# analog_filterung.net
KiCad netlist of a schematic drawn in Altium Designer
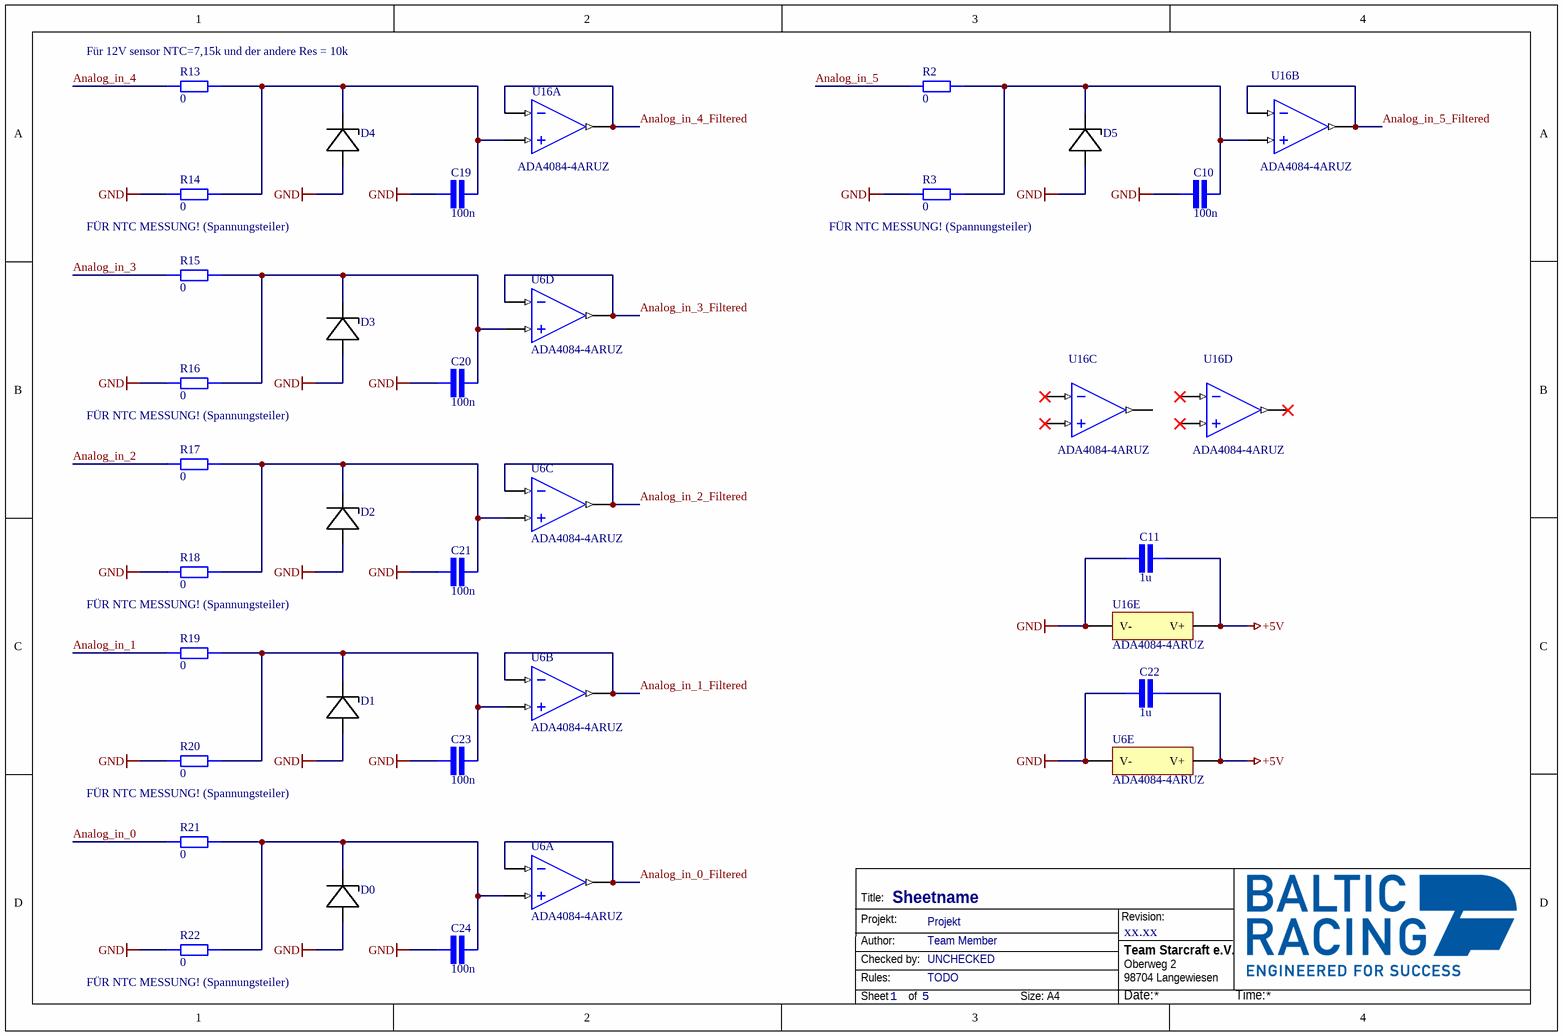
[diagram p0: analog filterung.SchDoc]

(export (version "E")
  (design (tool "Eeschema 10.0.6"))
  (components
    (comp (ref "C10")
      (value "100n")
      (footprint "CAP 0603/1608")
      (description "Capacitor with multiple Footprints")
      (fields (field (name "Comment") "SMD Capacitor"))
      (libsource (lib "") (part "SMD Capacitor_1"))
    )
    (comp (ref "C11")
      (value "1u")
      (footprint "CAP 0603/1608")
      (description "Capacitor with multiple Footprints")
      (fields (field (name "Comment") "SMD Capacitor"))
      (libsource (lib "Standardbauteile") (part "SMD Capacitor"))
    )
    (comp (ref "C19")
      (value "100n")
      (footprint "CAP 0603/1608")
      (description "Capacitor with multiple Footprints")
      (fields (field (name "Comment") "SMD Capacitor"))
      (libsource (lib "") (part "SMD Capacitor_1"))
    )
    (comp (ref "C20")
      (value "100n")
      (footprint "CAP 0603/1608")
      (description "Capacitor with multiple Footprints")
      (fields (field (name "Comment") "SMD Capacitor"))
      (libsource (lib "") (part "SMD Capacitor_1"))
    )
    (comp (ref "C21")
      (value "100n")
      (footprint "CAP 0603/1608")
      (description "Capacitor with multiple Footprints")
      (fields (field (name "Comment") "SMD Capacitor"))
      (libsource (lib "") (part "SMD Capacitor_1"))
    )
    (comp (ref "C22")
      (value "1u")
      (footprint "CAP 0603/1608")
      (description "Capacitor with multiple Footprints")
      (fields (field (name "Comment") "SMD Capacitor"))
      (libsource (lib "Standardbauteile") (part "SMD Capacitor"))
    )
    (comp (ref "C23")
      (value "100n")
      (footprint "CAP 0603/1608")
      (description "Capacitor with multiple Footprints")
      (fields (field (name "Comment") "SMD Capacitor"))
      (libsource (lib "") (part "SMD Capacitor_1"))
    )
    (comp (ref "C24")
      (value "100n")
      (footprint "CAP 0603/1608")
      (description "Capacitor with multiple Footprints")
      (fields (field (name "Comment") "SMD Capacitor"))
      (libsource (lib "") (part "SMD Capacitor_1"))
    )
    (comp (ref "D0")
      (value "MMBZ4625-HE3-08")
      (footprint "SOT95P248X115-3N")
      (description "Zener-Diode 5.1 Volt 0.225W 5% AUTO")
      (libsource (lib "LibMoritz") (part "MMBZ4625-HE3-08"))
    )
    (comp (ref "D1")
      (value "MMBZ4625-HE3-08")
      (footprint "SOT95P248X115-3N")
      (description "Zener-Diode 5.1 Volt 0.225W 5% AUTO")
      (libsource (lib "LibMoritz") (part "MMBZ4625-HE3-08"))
    )
    (comp (ref "D2")
      (value "MMBZ4625-HE3-08")
      (footprint "SOT95P248X115-3N")
      (description "Zener-Diode 5.1 Volt 0.225W 5% AUTO")
      (libsource (lib "LibMoritz") (part "MMBZ4625-HE3-08"))
    )
    (comp (ref "D3")
      (value "MMBZ4625-HE3-08")
      (footprint "SOT95P248X115-3N")
      (description "Zener-Diode 5.1 Volt 0.225W 5% AUTO")
      (libsource (lib "LibMoritz") (part "MMBZ4625-HE3-08"))
    )
    (comp (ref "D4")
      (value "MMBZ4625-HE3-08")
      (footprint "SOT95P248X115-3N")
      (description "Zener-Diode 5.1 Volt 0.225W 5% AUTO")
      (libsource (lib "LibMoritz") (part "MMBZ4625-HE3-08"))
    )
    (comp (ref "D5")
      (value "MMBZ4625-HE3-08")
      (footprint "SOT95P248X115-3N")
      (description "Zener-Diode 5.1 Volt 0.225W 5% AUTO")
      (libsource (lib "LibMoritz") (part "MMBZ4625-HE3-08"))
    )
    (comp (ref "R2")
      (value "0")
      (footprint "STACKPOLE CSR0603")
      (description "Resistor with multiple footprints")
      (fields (field (name "Comment") "SMD Resistor"))
      (libsource (lib "Standardbauteile") (part "SMD Resistor"))
    )
    (comp (ref "R3")
      (value "0")
      (footprint "STACKPOLE CSR0603")
      (description "Resistor with multiple footprints")
      (fields (field (name "Comment") "SMD Resistor"))
      (libsource (lib "Standardbauteile") (part "SMD Resistor"))
    )
    (comp (ref "R13")
      (value "0")
      (footprint "STACKPOLE CSR0603")
      (description "Resistor with multiple footprints")
      (fields (field (name "Comment") "SMD Resistor"))
      (libsource (lib "Standardbauteile") (part "SMD Resistor"))
    )
    (comp (ref "R14")
      (value "0")
      (footprint "STACKPOLE CSR0603")
      (description "Resistor with multiple footprints")
      (fields (field (name "Comment") "SMD Resistor"))
      (libsource (lib "Standardbauteile") (part "SMD Resistor"))
    )
    (comp (ref "R15")
      (value "0")
      (footprint "STACKPOLE CSR0603")
      (description "Resistor with multiple footprints")
      (fields (field (name "Comment") "SMD Resistor"))
      (libsource (lib "Standardbauteile") (part "SMD Resistor"))
    )
    (comp (ref "R16")
      (value "0")
      (footprint "STACKPOLE CSR0603")
      (description "Resistor with multiple footprints")
      (fields (field (name "Comment") "SMD Resistor"))
      (libsource (lib "Standardbauteile") (part "SMD Resistor"))
    )
    (comp (ref "R17")
      (value "0")
      (footprint "STACKPOLE CSR0603")
      (description "Resistor with multiple footprints")
      (fields (field (name "Comment") "SMD Resistor"))
      (libsource (lib "Standardbauteile") (part "SMD Resistor"))
    )
    (comp (ref "R18")
      (value "0")
      (footprint "STACKPOLE CSR0603")
      (description "Resistor with multiple footprints")
      (fields (field (name "Comment") "SMD Resistor"))
      (libsource (lib "Standardbauteile") (part "SMD Resistor"))
    )
    (comp (ref "R19")
      (value "0")
      (footprint "STACKPOLE CSR0603")
      (description "Resistor with multiple footprints")
      (fields (field (name "Comment") "SMD Resistor"))
      (libsource (lib "Standardbauteile") (part "SMD Resistor"))
    )
    (comp (ref "R20")
      (value "0")
      (footprint "STACKPOLE CSR0603")
      (description "Resistor with multiple footprints")
      (fields (field (name "Comment") "SMD Resistor"))
      (libsource (lib "Standardbauteile") (part "SMD Resistor"))
    )
    (comp (ref "R21")
      (value "0")
      (footprint "STACKPOLE CSR0603")
      (description "Resistor with multiple footprints")
      (fields (field (name "Comment") "SMD Resistor"))
      (libsource (lib "Standardbauteile") (part "SMD Resistor"))
    )
    (comp (ref "R22")
      (value "0")
      (footprint "STACKPOLE CSR0603")
      (description "Resistor with multiple footprints")
      (fields (field (name "Comment") "SMD Resistor"))
      (libsource (lib "Standardbauteile") (part "SMD Resistor"))
    )
    (comp (ref "U6")
      (value "ADA4084-4ARUZ")
      (footprint "ANALOG_RU14")
      (description "30 V, Low Noise, Rail-to-Rail Input/Output, Low Power Operational Amplifiers")
      (libsource (lib "Standardbauteile") (part "ADA4084-4ARUZ"))
    )
    (comp (ref "U16")
      (value "ADA4084-4ARUZ")
      (footprint "ANALOG_RU14")
      (description "30 V, Low Noise, Rail-to-Rail Input/Output, Low Power Operational Amplifiers")
      (libsource (lib "Standardbauteile") (part "ADA4084-4ARUZ"))
    )
  )
  (nets
    (net (code "1") (name "+5V") (class "Default")
      (node (ref "C11") (pin "1") (pinfunction "1_1") (pintype "passive"))
      (node (ref "C22") (pin "1") (pinfunction "1_1") (pintype "passive"))
      (node (ref "U16") (pin "4") (pinfunction "V+_4") (pintype "power_in"))
      (node (ref "U6") (pin "4") (pinfunction "V+_4") (pintype "power_in"))
    )
    (net (code "2") (name "/Analog_in_0") (class "Default")
      (node (ref "R21") (pin "2") (pinfunction "2_2") (pintype "passive"))
    )
    (net (code "3") (name "/Analog_in_0_Filtered") (class "Default")
      (node (ref "U6") (pin "1") (pinfunction "OUT_A_1") (pintype "output"))
      (node (ref "U6") (pin "2") (pinfunction "-IN_A_2") (pintype "input"))
    )
    (net (code "4") (name "/Analog_in_1") (class "Default")
      (node (ref "R19") (pin "2") (pinfunction "2_2") (pintype "passive"))
    )
    (net (code "5") (name "/Analog_in_1_Filtered") (class "Default")
      (node (ref "U6") (pin "6") (pinfunction "-IN_B_6") (pintype "input"))
      (node (ref "U6") (pin "7") (pinfunction "OUT_B_7") (pintype "output"))
    )
    (net (code "6") (name "/Analog_in_2") (class "Default")
      (node (ref "R17") (pin "2") (pinfunction "2_2") (pintype "passive"))
    )
    (net (code "7") (name "/Analog_in_2_Filtered") (class "Default")
      (node (ref "U6") (pin "8") (pinfunction "OUT_C_8") (pintype "output"))
      (node (ref "U6") (pin "9") (pinfunction "-IN_C_9") (pintype "input"))
    )
    (net (code "8") (name "/Analog_in_3") (class "Default")
      (node (ref "R15") (pin "2") (pinfunction "2_2") (pintype "passive"))
    )
    (net (code "9") (name "/Analog_in_3_Filtered") (class "Default")
      (node (ref "U6") (pin "13") (pinfunction "-IN_D_13") (pintype "input"))
      (node (ref "U6") (pin "14") (pinfunction "OUT_D_14") (pintype "output"))
    )
    (net (code "10") (name "/Analog_in_4") (class "Default")
      (node (ref "R13") (pin "2") (pinfunction "2_2") (pintype "passive"))
    )
    (net (code "11") (name "/Analog_in_4_Filtered") (class "Default")
      (node (ref "U16") (pin "1") (pinfunction "OUT_A_1") (pintype "output"))
      (node (ref "U16") (pin "2") (pinfunction "-IN_A_2") (pintype "input"))
    )
    (net (code "12") (name "/Analog_in_5") (class "Default")
      (node (ref "R2") (pin "2") (pinfunction "2_2") (pintype "passive"))
    )
    (net (code "13") (name "/Analog_in_5_Filtered") (class "Default")
      (node (ref "U16") (pin "6") (pinfunction "-IN_B_6") (pintype "input"))
      (node (ref "U16") (pin "7") (pinfunction "OUT_B_7") (pintype "output"))
    )
    (net (code "14") (name "GND") (class "Default")
      (node (ref "C10") (pin "1") (pinfunction "1_1") (pintype "passive"))
      (node (ref "C11") (pin "2") (pinfunction "2_2") (pintype "passive"))
      (node (ref "C19") (pin "1") (pinfunction "1_1") (pintype "passive"))
      (node (ref "C20") (pin "1") (pinfunction "1_1") (pintype "passive"))
      (node (ref "C21") (pin "1") (pinfunction "1_1") (pintype "passive"))
      (node (ref "C22") (pin "2") (pinfunction "2_2") (pintype "passive"))
      (node (ref "C23") (pin "1") (pinfunction "1_1") (pintype "passive"))
      (node (ref "C24") (pin "1") (pinfunction "1_1") (pintype "passive"))
      (node (ref "D0") (pin "A") (pinfunction "Anode_A") (pintype "passive"))
      (node (ref "D1") (pin "A") (pinfunction "Anode_A") (pintype "passive"))
      (node (ref "D2") (pin "A") (pinfunction "Anode_A") (pintype "passive"))
      (node (ref "D3") (pin "A") (pinfunction "Anode_A") (pintype "passive"))
      (node (ref "D4") (pin "A") (pinfunction "Anode_A") (pintype "passive"))
      (node (ref "D5") (pin "A") (pinfunction "Anode_A") (pintype "passive"))
      (node (ref "R14") (pin "2") (pinfunction "2_2") (pintype "passive"))
      (node (ref "R16") (pin "2") (pinfunction "2_2") (pintype "passive"))
      (node (ref "R18") (pin "2") (pinfunction "2_2") (pintype "passive"))
      (node (ref "R20") (pin "2") (pinfunction "2_2") (pintype "passive"))
      (node (ref "R22") (pin "2") (pinfunction "2_2") (pintype "passive"))
      (node (ref "R3") (pin "2") (pinfunction "2_2") (pintype "passive"))
      (node (ref "U16") (pin "11") (pinfunction "V-_11") (pintype "power_in"))
      (node (ref "U6") (pin "11") (pinfunction "V-_11") (pintype "power_in"))
    )
    (net (code "15") (name "Net-(D0-Kathode)") (class "Default")
      (node (ref "C24") (pin "2") (pinfunction "2_2") (pintype "passive"))
      (node (ref "D0") (pin "C") (pinfunction "Kathode_C") (pintype "passive"))
      (node (ref "R21") (pin "1") (pinfunction "1_1") (pintype "passive"))
      (node (ref "R22") (pin "1") (pinfunction "1_1") (pintype "passive"))
      (node (ref "U6") (pin "3") (pinfunction "+IN_A_3") (pintype "input"))
    )
    (net (code "16") (name "Net-(D1-Kathode)") (class "Default")
      (node (ref "C23") (pin "2") (pinfunction "2_2") (pintype "passive"))
      (node (ref "D1") (pin "C") (pinfunction "Kathode_C") (pintype "passive"))
      (node (ref "R19") (pin "1") (pinfunction "1_1") (pintype "passive"))
      (node (ref "R20") (pin "1") (pinfunction "1_1") (pintype "passive"))
      (node (ref "U6") (pin "5") (pinfunction "+IN_B_5") (pintype "input"))
    )
    (net (code "17") (name "Net-(D2-Kathode)") (class "Default")
      (node (ref "C21") (pin "2") (pinfunction "2_2") (pintype "passive"))
      (node (ref "D2") (pin "C") (pinfunction "Kathode_C") (pintype "passive"))
      (node (ref "R17") (pin "1") (pinfunction "1_1") (pintype "passive"))
      (node (ref "R18") (pin "1") (pinfunction "1_1") (pintype "passive"))
      (node (ref "U6") (pin "10") (pinfunction "+IN_C_10") (pintype "input"))
    )
    (net (code "18") (name "Net-(D3-Kathode)") (class "Default")
      (node (ref "C20") (pin "2") (pinfunction "2_2") (pintype "passive"))
      (node (ref "D3") (pin "C") (pinfunction "Kathode_C") (pintype "passive"))
      (node (ref "R15") (pin "1") (pinfunction "1_1") (pintype "passive"))
      (node (ref "R16") (pin "1") (pinfunction "1_1") (pintype "passive"))
      (node (ref "U6") (pin "12") (pinfunction "+IN_D_12") (pintype "input"))
    )
    (net (code "19") (name "Net-(D4-Kathode)") (class "Default")
      (node (ref "C19") (pin "2") (pinfunction "2_2") (pintype "passive"))
      (node (ref "D4") (pin "C") (pinfunction "Kathode_C") (pintype "passive"))
      (node (ref "R13") (pin "1") (pinfunction "1_1") (pintype "passive"))
      (node (ref "R14") (pin "1") (pinfunction "1_1") (pintype "passive"))
      (node (ref "U16") (pin "3") (pinfunction "+IN_A_3") (pintype "input"))
    )
    (net (code "20") (name "Net-(D5-Kathode)") (class "Default")
      (node (ref "C10") (pin "2") (pinfunction "2_2") (pintype "passive"))
      (node (ref "D5") (pin "C") (pinfunction "Kathode_C") (pintype "passive"))
      (node (ref "R2") (pin "1") (pinfunction "1_1") (pintype "passive"))
      (node (ref "R3") (pin "1") (pinfunction "1_1") (pintype "passive"))
      (node (ref "U16") (pin "5") (pinfunction "+IN_B_5") (pintype "input"))
    )
    (net (code "21") (name "unconnected-(U16C-+IN_C-Pad10)") (class "Default")
      (node (ref "U16") (pin "10") (pinfunction "+IN_C_10") (pintype "input+no_connect"))
    )
    (net (code "22") (name "unconnected-(U16C--IN_C-Pad9)") (class "Default")
      (node (ref "U16") (pin "9") (pinfunction "-IN_C_9") (pintype "input+no_connect"))
    )
    (net (code "23") (name "unconnected-(U16C-OUT_C-Pad8)") (class "Default")
      (node (ref "U16") (pin "8") (pinfunction "OUT_C_8") (pintype "output"))
    )
    (net (code "24") (name "unconnected-(U16D-+IN_D-Pad12)") (class "Default")
      (node (ref "U16") (pin "12") (pinfunction "+IN_D_12") (pintype "input+no_connect"))
    )
    (net (code "25") (name "unconnected-(U16D--IN_D-Pad13)") (class "Default")
      (node (ref "U16") (pin "13") (pinfunction "-IN_D_13") (pintype "input+no_connect"))
    )
    (net (code "26") (name "unconnected-(U16D-OUT_D-Pad14)") (class "Default")
      (node (ref "U16") (pin "14") (pinfunction "OUT_D_14") (pintype "output+no_connect"))
    )
  )
)
